# Schematic.net
KiCad netlist of a schematic drawn in EAGLE
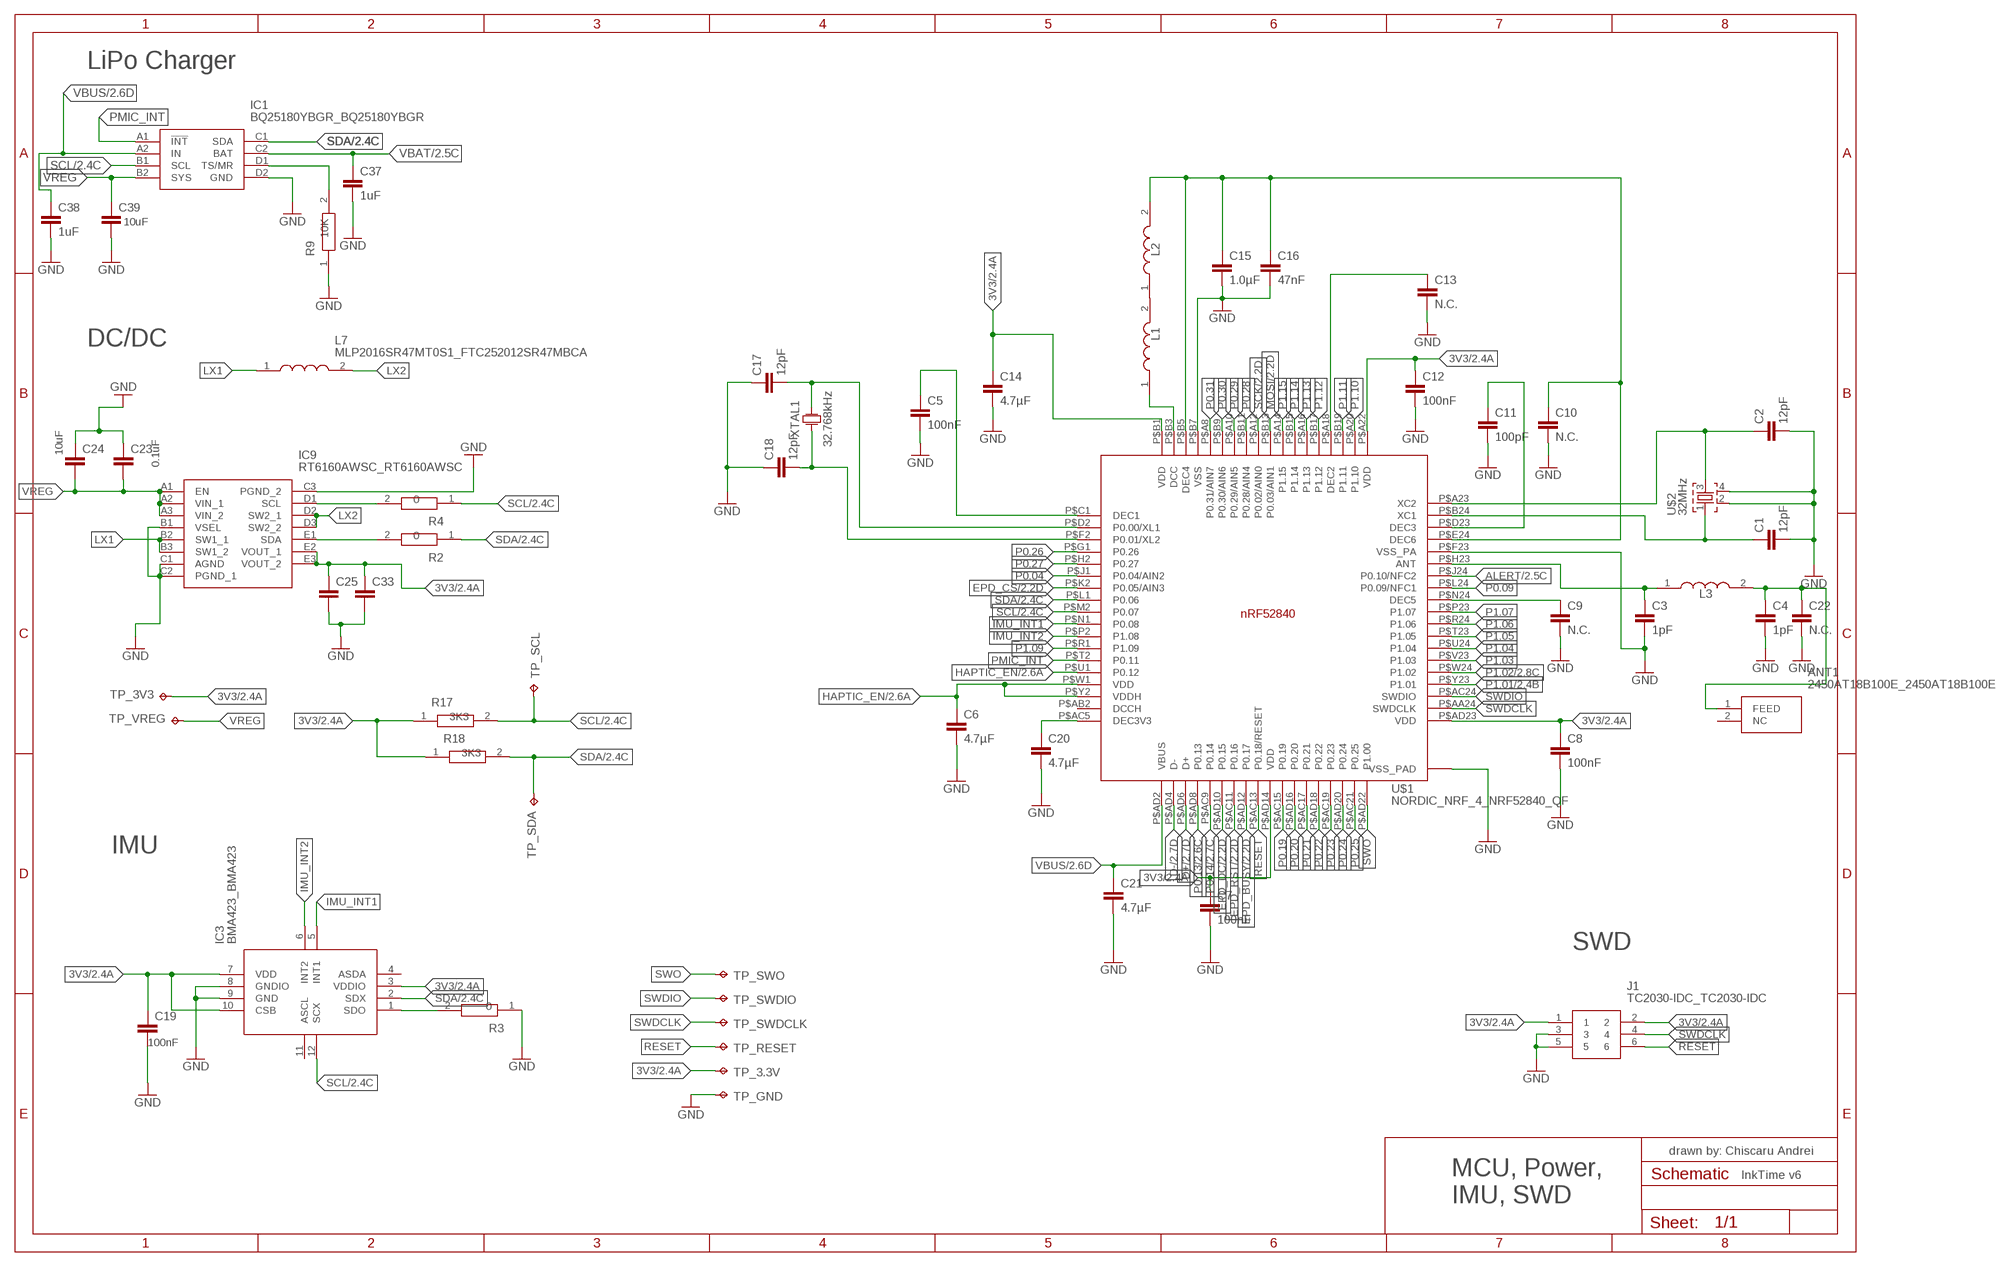
[diagram p0: schematic, sheet 1, part 1 of 2]
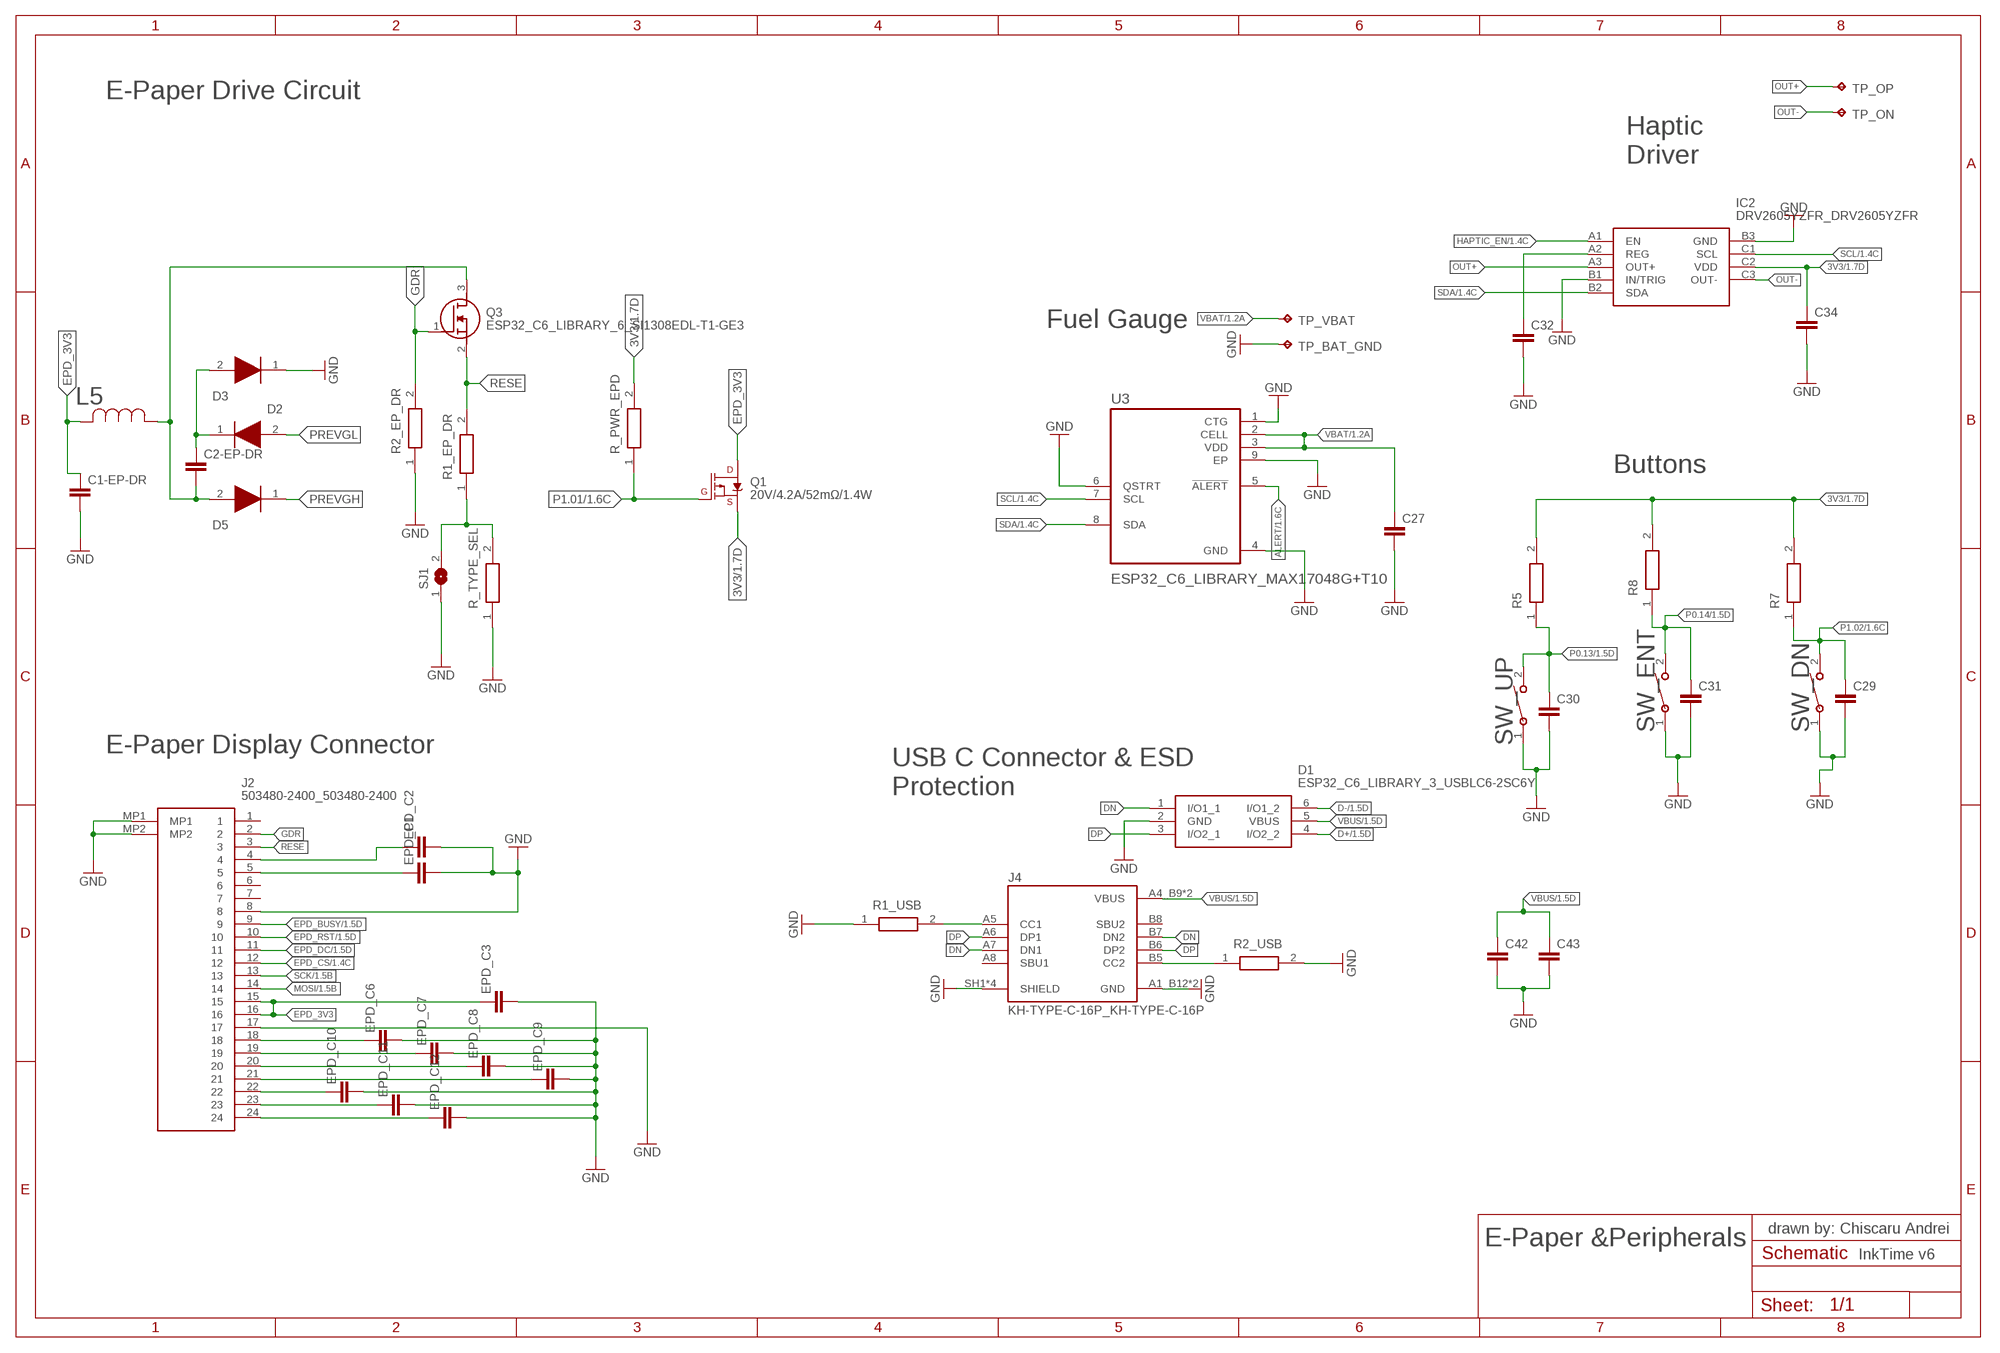
[diagram p1: schematic, sheet 1, part 2 of 2]

(export (version "E")
  (design (tool "Eeschema 10.0.6"))
  (components
    (comp (ref "ANT1")
      (value "2450AT18B100E_2450AT18B100E")
      (footprint "eagle-import:2450AT18B100E_ANTC3216X140N")
      (fields
        (field (name "ARROW_PART_NUMBER") "2450AT18B100E")
        (field (name "MOUSER_PART_NUMBER") "609-2450AT18B100E")
      )
      (libsource (lib "eagle-import") (part "2450AT18B100E_2450AT18B100E"))
    )
    (comp (ref "C1")
      (value "12pF")
      (footprint "eagle-import:NORDIC_NRF_3_RESC0201_L")
      (libsource (lib "eagle-import") (part "NORDIC_NRF_3_CAPACITOR_0201_L"))
    )
    (comp (ref "C1-EP-DR")
      (value "10uF")
      (footprint "eagle-import:NORDIC_NRF_3_RESC0201_L")
      (libsource (lib "eagle-import") (part "NORDIC_NRF_3_CAPACITOR_0201_L"))
    )
    (comp (ref "C2")
      (value "12pF")
      (footprint "eagle-import:NORDIC_NRF_3_RESC0201_L")
      (libsource (lib "eagle-import") (part "NORDIC_NRF_3_CAPACITOR_0201_L"))
    )
    (comp (ref "C2-EP-DR")
      (value "4.7uF/25V")
      (footprint "eagle-import:NORDIC_NRF_3_RESC0201_L")
      (libsource (lib "eagle-import") (part "NORDIC_NRF_3_CAPACITOR_0201_L"))
    )
    (comp (ref "C3")
      (value "1pF")
      (footprint "eagle-import:NORDIC_NRF_3_RESC0201_L")
      (libsource (lib "eagle-import") (part "NORDIC_NRF_3_CAPACITOR_0201_L"))
    )
    (comp (ref "C4")
      (value "1pF")
      (footprint "eagle-import:NORDIC_NRF_3_RESC0201_L")
      (libsource (lib "eagle-import") (part "NORDIC_NRF_3_CAPACITOR_0201_L"))
    )
    (comp (ref "C5")
      (value "100nF")
      (footprint "eagle-import:NORDIC_NRF_3_RESC0201_L")
      (libsource (lib "eagle-import") (part "NORDIC_NRF_3_CAPACITOR_0201_L"))
    )
    (comp (ref "C6")
      (value "4.7µF")
      (footprint "eagle-import:NORDIC_NRF_3_RESC0201_L")
      (libsource (lib "eagle-import") (part "NORDIC_NRF_3_CAPACITOR_0201_L"))
    )
    (comp (ref "C7")
      (value "100nF")
      (footprint "eagle-import:NORDIC_NRF_3_RESC0201_L")
      (libsource (lib "eagle-import") (part "NORDIC_NRF_3_CAPACITOR_0201_L"))
    )
    (comp (ref "C8")
      (value "100nF")
      (footprint "eagle-import:NORDIC_NRF_3_RESC0201_L")
      (libsource (lib "eagle-import") (part "NORDIC_NRF_3_CAPACITOR_0201_L"))
    )
    (comp (ref "C9")
      (value "N.C.")
      (footprint "eagle-import:NORDIC_NRF_3_RESC0201_L")
      (libsource (lib "eagle-import") (part "NORDIC_NRF_3_CAPACITOR_0201_L"))
    )
    (comp (ref "C10")
      (value "N.C.")
      (footprint "eagle-import:NORDIC_NRF_3_RESC0201_L")
      (libsource (lib "eagle-import") (part "NORDIC_NRF_3_CAPACITOR_0201_L"))
    )
    (comp (ref "C11")
      (value "100pF")
      (footprint "eagle-import:NORDIC_NRF_3_RESC0201_L")
      (libsource (lib "eagle-import") (part "NORDIC_NRF_3_CAPACITOR_0201_L"))
    )
    (comp (ref "C12")
      (value "100nF")
      (footprint "eagle-import:NORDIC_NRF_3_RESC0201_L")
      (libsource (lib "eagle-import") (part "NORDIC_NRF_3_CAPACITOR_0201_L"))
    )
    (comp (ref "C13")
      (value "N.C.")
      (footprint "eagle-import:NORDIC_NRF_3_RESC0201_L")
      (libsource (lib "eagle-import") (part "NORDIC_NRF_3_CAPACITOR_0201_L"))
    )
    (comp (ref "C14")
      (value "4.7µF")
      (footprint "eagle-import:NORDIC_NRF_3_RESC0201_L")
      (libsource (lib "eagle-import") (part "NORDIC_NRF_3_CAPACITOR_0201_L"))
    )
    (comp (ref "C15")
      (value "1.0µF")
      (footprint "eagle-import:NORDIC_NRF_3_RESC0201_L")
      (libsource (lib "eagle-import") (part "NORDIC_NRF_3_CAPACITOR_0201_L"))
    )
    (comp (ref "C16")
      (value "47nF")
      (footprint "eagle-import:NORDIC_NRF_3_RESC0201_L")
      (libsource (lib "eagle-import") (part "NORDIC_NRF_3_CAPACITOR_0201_L"))
    )
    (comp (ref "C17")
      (value "12pF")
      (footprint "eagle-import:NORDIC_NRF_3_RESC0201_L")
      (libsource (lib "eagle-import") (part "NORDIC_NRF_3_CAPACITOR_0201_L"))
    )
    (comp (ref "C18")
      (value "12pF")
      (footprint "eagle-import:NORDIC_NRF_3_RESC0201_L")
      (libsource (lib "eagle-import") (part "NORDIC_NRF_3_CAPACITOR_0201_L"))
    )
    (comp (ref "C19")
      (value "100nF")
      (footprint "eagle-import:NORDIC_NRF_3_RESC0201_L")
      (libsource (lib "eagle-import") (part "NORDIC_NRF_3_CAPACITOR_0201_L"))
    )
    (comp (ref "C20")
      (value "4.7µF")
      (footprint "eagle-import:NORDIC_NRF_3_RESC0201_L")
      (libsource (lib "eagle-import") (part "NORDIC_NRF_3_CAPACITOR_0201_L"))
    )
    (comp (ref "C21")
      (value "4.7µF")
      (footprint "eagle-import:NORDIC_NRF_3_RESC0201_L")
      (libsource (lib "eagle-import") (part "NORDIC_NRF_3_CAPACITOR_0201_L"))
    )
    (comp (ref "C22")
      (value "N.C.")
      (footprint "eagle-import:NORDIC_NRF_3_RESC0201_L")
      (libsource (lib "eagle-import") (part "NORDIC_NRF_3_CAPACITOR_0201_L"))
    )
    (comp (ref "C23")
      (value "0.1uF")
      (footprint "eagle-import:NORDIC_NRF_3_RESC0201_L")
      (libsource (lib "eagle-import") (part "NORDIC_NRF_3_CAPACITOR_0201_L"))
    )
    (comp (ref "C24")
      (value "10uF")
      (footprint "eagle-import:NORDIC_NRF_3_RESC0201_L")
      (libsource (lib "eagle-import") (part "NORDIC_NRF_3_CAPACITOR_0201_L"))
    )
    (comp (ref "C25")
      (value "22uF")
      (footprint "eagle-import:NORDIC_NRF_3_RESC0201_L")
      (libsource (lib "eagle-import") (part "NORDIC_NRF_3_CAPACITOR_0201_L"))
    )
    (comp (ref "C27")
      (value "0.1uF")
      (footprint "eagle-import:NORDIC_NRF_3_RESC0201_L")
      (libsource (lib "eagle-import") (part "NORDIC_NRF_3_CAPACITOR_0201_L"))
    )
    (comp (ref "C29")
      (value "1uF")
      (footprint "eagle-import:NORDIC_NRF_3_RESC0201_L")
      (libsource (lib "eagle-import") (part "NORDIC_NRF_3_CAPACITOR_0201_L"))
    )
    (comp (ref "C30")
      (value "1uF")
      (footprint "eagle-import:NORDIC_NRF_3_RESC0201_L")
      (libsource (lib "eagle-import") (part "NORDIC_NRF_3_CAPACITOR_0201_L"))
    )
    (comp (ref "C31")
      (value "1uF")
      (footprint "eagle-import:NORDIC_NRF_3_RESC0201_L")
      (libsource (lib "eagle-import") (part "NORDIC_NRF_3_CAPACITOR_0201_L"))
    )
    (comp (ref "C32")
      (value "1uF")
      (footprint "eagle-import:NORDIC_NRF_3_RESC0201_L")
      (libsource (lib "eagle-import") (part "NORDIC_NRF_3_CAPACITOR_0201_L"))
    )
    (comp (ref "C33")
      (value "22uF")
      (footprint "eagle-import:NORDIC_NRF_3_RESC0201_L")
      (libsource (lib "eagle-import") (part "NORDIC_NRF_3_CAPACITOR_0201_L"))
    )
    (comp (ref "C34")
      (value "0.1uF")
      (footprint "eagle-import:NORDIC_NRF_3_RESC0201_L")
      (libsource (lib "eagle-import") (part "NORDIC_NRF_3_CAPACITOR_0201_L"))
    )
    (comp (ref "C37")
      (value "1uF")
      (footprint "eagle-import:NORDIC_NRF_3_RESC0201_L")
      (libsource (lib "eagle-import") (part "NORDIC_NRF_3_CAPACITOR_0201_L"))
    )
    (comp (ref "C38")
      (value "1uF")
      (footprint "eagle-import:NORDIC_NRF_3_RESC0201_L")
      (libsource (lib "eagle-import") (part "NORDIC_NRF_3_CAPACITOR_0201_L"))
    )
    (comp (ref "C39")
      (value "10uF")
      (footprint "eagle-import:NORDIC_NRF_3_RESC0201_L")
      (libsource (lib "eagle-import") (part "NORDIC_NRF_3_CAPACITOR_0201_L"))
    )
    (comp (ref "C42")
      (value "0.1uF")
      (footprint "eagle-import:NORDIC_NRF_3_RESC0201_L")
      (libsource (lib "eagle-import") (part "NORDIC_NRF_3_CAPACITOR_0201_L"))
    )
    (comp (ref "C43")
      (value "4.7uF")
      (footprint "eagle-import:NORDIC_NRF_3_RESC0201_L")
      (libsource (lib "eagle-import") (part "NORDIC_NRF_3_CAPACITOR_0201_L"))
    )
    (comp (ref "D1")
      (value "ESP32_C6_LIBRARY_3_USBLC6-2SC6Y")
      (footprint "eagle-import:ESP32_C6_LIBRARY_3_SOT95P280X145-6N")
      (fields (field (name "MF") "STMicroelectronics") (field (name "MP") "USBLC6-2SC6Y"))
      (libsource (lib "eagle-import") (part "ESP32_C6_LIBRARY_3_USBLC6-2SC6Y"))
    )
    (comp (ref "D2")
      (value "ESP32_C6_LIBRARY_5_MBR0530")
      (footprint "eagle-import:ESP32_C6_LIBRARY_5_SOD3716X135N")
      (fields (field (name "MF") "ON Semiconductor") (field (name "MP") "MBR0530"))
      (libsource (lib "eagle-import") (part "ESP32_C6_LIBRARY_5_MBR0530"))
    )
    (comp (ref "D3")
      (value "ESP32_C6_LIBRARY_5_MBR0530")
      (footprint "eagle-import:ESP32_C6_LIBRARY_5_SOD3716X135N")
      (fields (field (name "MF") "ON Semiconductor") (field (name "MP") "MBR0530"))
      (libsource (lib "eagle-import") (part "ESP32_C6_LIBRARY_5_MBR0530"))
    )
    (comp (ref "D5")
      (value "ESP32_C6_LIBRARY_5_MBR0530")
      (footprint "eagle-import:ESP32_C6_LIBRARY_5_SOD3716X135N")
      (fields (field (name "MF") "ON Semiconductor") (field (name "MP") "MBR0530"))
      (libsource (lib "eagle-import") (part "ESP32_C6_LIBRARY_5_MBR0530"))
    )
    (comp (ref "EPD_C1")
      (value "1uF/50V")
      (footprint "eagle-import:NORDIC_NRF_3_RESC0201_L")
      (libsource (lib "eagle-import") (part "NORDIC_NRF_3_CAPACITOR_0201_L"))
    )
    (comp (ref "EPD_C2")
      (value "1uF/50V")
      (footprint "eagle-import:NORDIC_NRF_3_RESC0201_L")
      (libsource (lib "eagle-import") (part "NORDIC_NRF_3_CAPACITOR_0201_L"))
    )
    (comp (ref "EPD_C3")
      (value "0.1uF/50V")
      (footprint "eagle-import:NORDIC_NRF_3_RESC0201_L")
      (libsource (lib "eagle-import") (part "NORDIC_NRF_3_CAPACITOR_0201_L"))
    )
    (comp (ref "EPD_C6")
      (value "1uF/50V")
      (footprint "eagle-import:NORDIC_NRF_3_RESC0201_L")
      (libsource (lib "eagle-import") (part "NORDIC_NRF_3_CAPACITOR_0201_L"))
    )
    (comp (ref "EPD_C7")
      (value "1uF/50V")
      (footprint "eagle-import:NORDIC_NRF_3_RESC0201_L")
      (libsource (lib "eagle-import") (part "NORDIC_NRF_3_CAPACITOR_0201_L"))
    )
    (comp (ref "EPD_C8")
      (value "1uF/50V")
      (footprint "eagle-import:NORDIC_NRF_3_RESC0201_L")
      (libsource (lib "eagle-import") (part "NORDIC_NRF_3_CAPACITOR_0201_L"))
    )
    (comp (ref "EPD_C9")
      (value "1uF/50V")
      (footprint "eagle-import:NORDIC_NRF_3_RESC0201_L")
      (libsource (lib "eagle-import") (part "NORDIC_NRF_3_CAPACITOR_0201_L"))
    )
    (comp (ref "EPD_C10")
      (value "1uF/50V")
      (footprint "eagle-import:NORDIC_NRF_3_RESC0201_L")
      (libsource (lib "eagle-import") (part "NORDIC_NRF_3_CAPACITOR_0201_L"))
    )
    (comp (ref "EPD_C11")
      (value "1uF/50V")
      (footprint "eagle-import:NORDIC_NRF_3_RESC0201_L")
      (libsource (lib "eagle-import") (part "NORDIC_NRF_3_CAPACITOR_0201_L"))
    )
    (comp (ref "EPD_C12")
      (value "1uF/50V")
      (footprint "eagle-import:NORDIC_NRF_3_RESC0201_L")
      (libsource (lib "eagle-import") (part "NORDIC_NRF_3_CAPACITOR_0201_L"))
    )
    (comp (ref "IC1")
      (value "BQ25180YBGR_BQ25180YBGR")
      (footprint "eagle-import:BQ25180YBGR_BGA8C40P2X4_100X155X50")
      (fields
        (field (name "ARROW_PART_NUMBER") "BQ25180YBGR")
        (field (name "MOUSER_PART_NUMBER") "595-BQ25180YBGR")
      )
      (libsource (lib "eagle-import") (part "BQ25180YBGR_BQ25180YBGR"))
    )
    (comp (ref "IC2")
      (value "DRV2605YZFR_DRV2605YZFR")
      (footprint "eagle-import:DRV2605YZFR_BGA9C50P3X3_144X144X62")
      (fields (field (name "ARROW_PART_NUMBER") "DRV2605YZFR"))
      (libsource (lib "eagle-import") (part "DRV2605YZFR_DRV2605YZFR"))
    )
    (comp (ref "IC3")
      (value "BMA423_BMA423")
      (footprint "eagle-import:BMA423_BMA423")
      (fields (field (name "ARROW_PART_NUMBER") "BMA423") (field (name "MOUSER_PART_NUMBER") "262-BMA423"))
      (libsource (lib "eagle-import") (part "BMA423_BMA423"))
    )
    (comp (ref "IC9")
      (value "RT6160AWSC_RT6160AWSC")
      (footprint "eagle-import:RT6160AWSC_BGA15C40P3X5_140X230X60")
      (fields
        (field (name "MANUFACTURER_PART_NUMBER") "RT6160AWSC")
        (field (name "MOUSER_PART_NUMBER") "835-RT6160AWSC")
      )
      (libsource (lib "eagle-import") (part "RT6160AWSC_RT6160AWSC"))
    )
    (comp (ref "J1")
      (value "TC2030-IDC_TC2030-IDC")
      (footprint "eagle-import:TC2030-IDC_TC2030IDC")
      (fields (field (name "MANUFACTURER_PART_NUMBER") "TC2030-IDC"))
      (libsource (lib "eagle-import") (part "TC2030-IDC_TC2030-IDC"))
    )
    (comp (ref "J2")
      (value "503480-2400_503480-2400")
      (footprint "eagle-import:503480-2400_5034802400")
      (fields
        (field (name "MANUFACTURER_PART_NUMBER") "503480-2400")
        (field (name "MOUSER_PART_NUMBER") "538-503480-2400")
      )
      (libsource (lib "eagle-import") (part "503480-2400_503480-2400"))
    )
    (comp (ref "J4")
      (value "KH-TYPE-C-16P_KH-TYPE-C-16P")
      (footprint "eagle-import:KH-TYPE-C-16P_KINGHELM_KH-TYPE-C-16P")
      (fields (field (name "MF") "kinghelm") (field (name "MP") "KH-TYPE-C-16P"))
      (libsource (lib "eagle-import") (part "KH-TYPE-C-16P_KH-TYPE-C-16P"))
    )
    (comp (ref "L1")
      (value "10µH")
      (footprint "eagle-import:MLP2016SR47MT0S1_INDC2016X100N")
      (fields (field (name "MANUFACTURER_PART_NUMBER") "FTC252012SR47MBCA"))
      (libsource (lib "eagle-import") (part "MLP2016SR47MT0S1_FTC252012SR47MBCA"))
    )
    (comp (ref "L2")
      (value "15nH")
      (footprint "eagle-import:MLP2016SR47MT0S1_INDC2016X100N")
      (fields (field (name "MANUFACTURER_PART_NUMBER") "FTC252012SR47MBCA"))
      (libsource (lib "eagle-import") (part "MLP2016SR47MT0S1_FTC252012SR47MBCA"))
    )
    (comp (ref "L3")
      (value "3.9nH")
      (footprint "eagle-import:MLP2016SR47MT0S1_INDC2016X100N")
      (fields (field (name "MANUFACTURER_PART_NUMBER") "FTC252012SR47MBCA"))
      (libsource (lib "eagle-import") (part "MLP2016SR47MT0S1_FTC252012SR47MBCA"))
    )
    (comp (ref "L5")
      (value "68uH")
      (footprint "eagle-import:ESP32_C6_LIBRARY_2_IND_4828-WE-TPC_WRE")
      (fields
        (field (name "MANUFACTURER_PART_NUMBER") "744043680")
        (field (name "COPYRIGHT") "Copyright (C) 2024 Ultra Librarian. All rights reserved.")
      )
      (libsource (lib "eagle-import") (part "ESP32_C6_LIBRARY_2_744043680IND_4828-WE-TPC_WRE"))
    )
    (comp (ref "L7")
      (value "MLP2016SR47MT0S1_FTC252012SR47MBCA")
      (footprint "eagle-import:MLP2016SR47MT0S1_INDC2016X100N")
      (fields (field (name "MANUFACTURER_PART_NUMBER") "FTC252012SR47MBCA"))
      (libsource (lib "eagle-import") (part "MLP2016SR47MT0S1_FTC252012SR47MBCA"))
    )
    (comp (ref "Q1")
      (value "20V/4.2A/52mΩ/1.4W")
      (footprint "eagle-import:ESP32_C6_LIBRARY_4_ESP32_C6_LIBRARY_4_ESP32_C6_LIBRARY_4_ESP32_C6_LIBRARY_4_ESP32_WROVER_SPARKFUN-DISCRETESEMI_SOT23-3")
      (libsource (lib "eagle-import") (part "ESP32_C6_LIBRARY_4_ESP32_WROVER_SPARKFUN-DISCRETESEMI_MOSFET_PCH-DMG2305UX-7"))
    )
    (comp (ref "Q3")
      (value "ESP32_C6_LIBRARY_6_SI1308EDL-T1-GE3")
      (footprint "eagle-import:ESP32_C6_LIBRARY_6_SOT65P210X110-3N")
      (fields (field (name "MF") "Vishay Siliconix") (field (name "MP") "SI1308EDL-T1-GE3"))
      (libsource (lib "eagle-import") (part "ESP32_C6_LIBRARY_6_SI1308EDL-T1-GE3"))
    )
    (comp (ref "R1_EP_DR")
      (value "0.47")
      (footprint "eagle-import:CPF0201D7K68C1_0201")
      (libsource (lib "eagle-import") (part "CPF0201D7K68C1_CPF0201D7K68C1"))
    )
    (comp (ref "R1_USB")
      (value "5K1")
      (footprint "eagle-import:CPF0201D7K68C1_0201")
      (libsource (lib "eagle-import") (part "CPF0201D7K68C1_CPF0201D7K68C1"))
    )
    (comp (ref "R2")
      (value "0")
      (footprint "eagle-import:CPF0201D7K68C1_0201")
      (libsource (lib "eagle-import") (part "CPF0201D7K68C1_CPF0201D7K68C1"))
    )
    (comp (ref "R2_EP_DR")
      (value "10K")
      (footprint "eagle-import:CPF0201D7K68C1_0201")
      (libsource (lib "eagle-import") (part "CPF0201D7K68C1_CPF0201D7K68C1"))
    )
    (comp (ref "R2_USB")
      (value "5K1")
      (footprint "eagle-import:CPF0201D7K68C1_0201")
      (libsource (lib "eagle-import") (part "CPF0201D7K68C1_CPF0201D7K68C1"))
    )
    (comp (ref "R3")
      (value "0")
      (footprint "eagle-import:CPF0201D7K68C1_0201")
      (libsource (lib "eagle-import") (part "CPF0201D7K68C1_CPF0201D7K68C1"))
    )
    (comp (ref "R4")
      (value "0")
      (footprint "eagle-import:CPF0201D7K68C1_0201")
      (libsource (lib "eagle-import") (part "CPF0201D7K68C1_CPF0201D7K68C1"))
    )
    (comp (ref "R5")
      (value "10K")
      (footprint "eagle-import:CPF0201D7K68C1_0201")
      (libsource (lib "eagle-import") (part "CPF0201D7K68C1_CPF0201D7K68C1"))
    )
    (comp (ref "R7")
      (value "10K")
      (footprint "eagle-import:CPF0201D7K68C1_0201")
      (libsource (lib "eagle-import") (part "CPF0201D7K68C1_CPF0201D7K68C1"))
    )
    (comp (ref "R8")
      (value "10K")
      (footprint "eagle-import:CPF0201D7K68C1_0201")
      (libsource (lib "eagle-import") (part "CPF0201D7K68C1_CPF0201D7K68C1"))
    )
    (comp (ref "R9")
      (value "10K")
      (footprint "eagle-import:CPF0201D7K68C1_0201")
      (libsource (lib "eagle-import") (part "CPF0201D7K68C1_CPF0201D7K68C1"))
    )
    (comp (ref "R17")
      (value "3K3")
      (footprint "eagle-import:CPF0201D7K68C1_0201")
      (libsource (lib "eagle-import") (part "CPF0201D7K68C1_CPF0201D7K68C1"))
    )
    (comp (ref "R18")
      (value "3K3")
      (footprint "eagle-import:CPF0201D7K68C1_0201")
      (libsource (lib "eagle-import") (part "CPF0201D7K68C1_CPF0201D7K68C1"))
    )
    (comp (ref "R_PWR_EPD")
      (value "10K")
      (footprint "eagle-import:CPF0201D7K68C1_0201")
      (libsource (lib "eagle-import") (part "CPF0201D7K68C1_CPF0201D7K68C1"))
    )
    (comp (ref "R_TYPE_SEL")
      (value "2.2")
      (footprint "eagle-import:CPF0201D7K68C1_0201")
      (libsource (lib "eagle-import") (part "CPF0201D7K68C1_CPF0201D7K68C1"))
    )
    (comp (ref "SJ1")
      (value "ESP32_C6_LIBRARY_7_JUMPER_SJ")
      (footprint "eagle-import:ESP32_C6_LIBRARY_7_JUMPER_SJ")
      (libsource (lib "eagle-import") (part "ESP32_C6_LIBRARY_7_JUMPER_SJ"))
    )
    (comp (ref "SW_DN")
      (value "2025-10-22_07-23-44_LIBRARY_EVP-AKE31ASW_EVP-AKE31A_PAN")
      (footprint "eagle-import:2025-10-22_07-23-44_LIBRARY_SW_EVP-AKE31A_PAN")
      (fields
        (field (name "MANUFACTURER_PART_NUMBER") "EVP-AKE31A")
        (field (name "COPYRIGHT") "Copyright (C) 2025 Ultra Librarian. All rights reserved.")
      )
      (libsource (lib "eagle-import") (part "2025-10-22_07-23-44_LIBRARY_EVP-AKE31ASW_EVP-AKE31A_PAN"))
    )
    (comp (ref "SW_ENT")
      (value "2025-10-22_07-23-44_LIBRARY_EVP-AKE31ASW_EVP-AKE31A_PAN")
      (footprint "eagle-import:2025-10-22_07-23-44_LIBRARY_SW_EVP-AKE31A_PAN")
      (fields
        (field (name "MANUFACTURER_PART_NUMBER") "EVP-AKE31A")
        (field (name "COPYRIGHT") "Copyright (C) 2025 Ultra Librarian. All rights reserved.")
      )
      (libsource (lib "eagle-import") (part "2025-10-22_07-23-44_LIBRARY_EVP-AKE31ASW_EVP-AKE31A_PAN"))
    )
    (comp (ref "SW_UP")
      (value "2025-10-22_07-23-44_LIBRARY_EVP-AKE31ASW_EVP-AKE31A_PAN")
      (footprint "eagle-import:2025-10-22_07-23-44_LIBRARY_SW_EVP-AKE31A_PAN")
      (fields
        (field (name "MANUFACTURER_PART_NUMBER") "EVP-AKE31A")
        (field (name "COPYRIGHT") "Copyright (C) 2025 Ultra Librarian. All rights reserved.")
      )
      (libsource (lib "eagle-import") (part "2025-10-22_07-23-44_LIBRARY_EVP-AKE31ASW_EVP-AKE31A_PAN"))
    )
    (comp (ref "TP_3.3V")
      (value "HECTOR_WATCH_1_TPTP20R")
      (footprint "eagle-import:HECTOR_WATCH_1_TP20R")
      (libsource (lib "eagle-import") (part "HECTOR_WATCH_1_TPTP20R"))
    )
    (comp (ref "TP_3V3")
      (value "HECTOR_WATCH_1_TPTP20R")
      (footprint "eagle-import:HECTOR_WATCH_1_TP20R")
      (libsource (lib "eagle-import") (part "HECTOR_WATCH_1_TPTP20R"))
    )
    (comp (ref "TP_BAT_GND")
      (value "HECTOR_WATCH_1_TPTP20R")
      (footprint "eagle-import:HECTOR_WATCH_1_TP20R")
      (libsource (lib "eagle-import") (part "HECTOR_WATCH_1_TPTP20R"))
    )
    (comp (ref "TP_GND")
      (value "HECTOR_WATCH_1_TPTP20R")
      (footprint "eagle-import:HECTOR_WATCH_1_TP20R")
      (libsource (lib "eagle-import") (part "HECTOR_WATCH_1_TPTP20R"))
    )
    (comp (ref "TP_ON")
      (value "HECTOR_WATCH_1_TPTP20R")
      (footprint "eagle-import:HECTOR_WATCH_1_TP20R")
      (libsource (lib "eagle-import") (part "HECTOR_WATCH_1_TPTP20R"))
    )
    (comp (ref "TP_OP")
      (value "HECTOR_WATCH_1_TPTP20R")
      (footprint "eagle-import:HECTOR_WATCH_1_TP20R")
      (libsource (lib "eagle-import") (part "HECTOR_WATCH_1_TPTP20R"))
    )
    (comp (ref "TP_RESET")
      (value "HECTOR_WATCH_1_TPTP20R")
      (footprint "eagle-import:HECTOR_WATCH_1_TP20R")
      (libsource (lib "eagle-import") (part "HECTOR_WATCH_1_TPTP20R"))
    )
    (comp (ref "TP_SCL")
      (value "HECTOR_WATCH_1_TPTP20R")
      (footprint "eagle-import:HECTOR_WATCH_1_TP20R")
      (libsource (lib "eagle-import") (part "HECTOR_WATCH_1_TPTP20R"))
    )
    (comp (ref "TP_SDA")
      (value "HECTOR_WATCH_1_TPTP20R")
      (footprint "eagle-import:HECTOR_WATCH_1_TP20R")
      (libsource (lib "eagle-import") (part "HECTOR_WATCH_1_TPTP20R"))
    )
    (comp (ref "TP_SWDCLK")
      (value "HECTOR_WATCH_1_TPTP20R")
      (footprint "eagle-import:HECTOR_WATCH_1_TP20R")
      (libsource (lib "eagle-import") (part "HECTOR_WATCH_1_TPTP20R"))
    )
    (comp (ref "TP_SWDIO")
      (value "HECTOR_WATCH_1_TPTP20R")
      (footprint "eagle-import:HECTOR_WATCH_1_TP20R")
      (libsource (lib "eagle-import") (part "HECTOR_WATCH_1_TPTP20R"))
    )
    (comp (ref "TP_SWO")
      (value "HECTOR_WATCH_1_TPTP20R")
      (footprint "eagle-import:HECTOR_WATCH_1_TP20R")
      (libsource (lib "eagle-import") (part "HECTOR_WATCH_1_TPTP20R"))
    )
    (comp (ref "TP_VBAT")
      (value "HECTOR_WATCH_1_TPTP20R")
      (footprint "eagle-import:HECTOR_WATCH_1_TP20R")
      (libsource (lib "eagle-import") (part "HECTOR_WATCH_1_TPTP20R"))
    )
    (comp (ref "TP_VREG")
      (value "HECTOR_WATCH_1_TPTP20R")
      (footprint "eagle-import:HECTOR_WATCH_1_TP20R")
      (libsource (lib "eagle-import") (part "HECTOR_WATCH_1_TPTP20R"))
    )
    (comp (ref "U$1")
      (value "NORDIC_NRF_4_NRF52840_QF")
      (footprint "eagle-import:NORDIC_NRF_4_AQFN50P700X700X85_HS-74N")
      (libsource (lib "eagle-import") (part "NORDIC_NRF_4_NRF52840_QF"))
    )
    (comp (ref "U$2")
      (value "32MHz")
      (footprint "eagle-import:NORDIC_NRF_BT-XTAL_2016_N")
      (libsource (lib "eagle-import") (part "NORDIC_NRF_XTAL_32MHZ"))
    )
    (comp (ref "U3")
      (value "ESP32_C6_LIBRARY_MAX17048G+T10")
      (footprint "eagle-import:ESP32_C6_LIBRARY_SON50P200X200X80-9N")
      (fields (field (name "MF") "Analog Devices") (field (name "MP") "MAX17048G+T10"))
      (libsource (lib "eagle-import") (part "ESP32_C6_LIBRARY_MAX17048G+T10"))
    )
    (comp (ref "XTAL1")
      (value "32.768kHz")
      (footprint "eagle-import:XTAL_ABS07-32.768KHZ-T")
      (fields
        (field (name "MANUFACTURER") "Abracon LLC")
        (field (name "MPN") "ABS07-32.768KHZ-T")
        (field (name "TOLERANCE") "±20 ppm")
      )
      (libsource (lib "eagle-import") (part "ABSO7"))
    )
  )
  (nets
    (net (code "1") (name "3V3{slash}1.7D") (class "Default")
      (node (ref "C34") (pin "1") (pinfunction "1_1") (pintype "passive"))
      (node (ref "IC2") (pin "C2") (pinfunction "VDD_C2") (pintype "bidirectional"))
      (node (ref "Q1") (pin "2") (pinfunction "S_2") (pintype "bidirectional"))
      (node (ref "R5") (pin "2") (pinfunction "2_2") (pintype "bidirectional"))
      (node (ref "R7") (pin "2") (pinfunction "2_2") (pintype "bidirectional"))
      (node (ref "R8") (pin "2") (pinfunction "2_2") (pintype "bidirectional"))
      (node (ref "R_PWR_EPD") (pin "2") (pinfunction "2_2") (pintype "bidirectional"))
    )
    (net (code "2") (name "3V3{slash}2.4A") (class "Default")
      (node (ref "C12") (pin "1") (pinfunction "1_1") (pintype "passive"))
      (node (ref "C14") (pin "1") (pinfunction "1_1") (pintype "passive"))
      (node (ref "C19") (pin "1") (pinfunction "1_1") (pintype "passive"))
      (node (ref "C25") (pin "1") (pinfunction "1_1") (pintype "passive"))
      (node (ref "C33") (pin "1") (pinfunction "1_1") (pintype "passive"))
      (node (ref "C7") (pin "1") (pinfunction "1_1") (pintype "passive"))
      (node (ref "C8") (pin "1") (pinfunction "1_1") (pintype "passive"))
      (node (ref "IC3") (pin "10") (pinfunction "CSB_10") (pintype "bidirectional"))
      (node (ref "IC3") (pin "3") (pinfunction "VDDIO_3") (pintype "bidirectional"))
      (node (ref "IC3") (pin "7") (pinfunction "VDD_7") (pintype "bidirectional"))
      (node (ref "IC9") (pin "E2") (pinfunction "VOUT_1_E2") (pintype "bidirectional"))
      (node (ref "IC9") (pin "E3") (pinfunction "VOUT_2_E3") (pintype "bidirectional"))
      (node (ref "J1") (pin "1") (pinfunction "1_1") (pintype "bidirectional"))
      (node (ref "R17") (pin "1") (pinfunction "1_1") (pintype "bidirectional"))
      (node (ref "R18") (pin "1") (pinfunction "1_1") (pintype "bidirectional"))
      (node (ref "TP_3.3V") (pin "TP") (pinfunction "TP_TP") (pintype "input"))
      (node (ref "TP_3V3") (pin "TP") (pinfunction "TP_TP") (pintype "input"))
      (node (ref "U$1") (pin "P$A22") (pinfunction "VDD_P$A22") (pintype "power_in"))
      (node (ref "U$1") (pin "P$AD14") (pinfunction "VDD_P$AD14") (pintype "power_in"))
      (node (ref "U$1") (pin "P$AD23") (pinfunction "VDD_P$AD23") (pintype "power_in"))
      (node (ref "U$1") (pin "P$B1") (pinfunction "VDD_P$B1") (pintype "power_in"))
    )
    (net (code "3") (name "ALERT{slash}1.6C") (class "Default")
      (node (ref "U3") (pin "5") (pinfunction "~{ALERT}_5") (pintype "output"))
    )
    (net (code "4") (name "ALERT{slash}2.5C") (class "Default")
      (node (ref "U$1") (pin "P$J24") (pinfunction "P0.10/NFC2_P$J24") (pintype "bidirectional"))
    )
    (net (code "5") (name "D+{slash}1.5D") (class "Default")
      (node (ref "D1") (pin "4") (pinfunction "I/O2_2_4") (pintype "bidirectional"))
    )
    (net (code "6") (name "D+{slash}2.7D") (class "Default")
      (node (ref "U$1") (pin "P$AD6") (pinfunction "D+_P$AD6") (pintype "bidirectional"))
    )
    (net (code "7") (name "D-{slash}1.5D") (class "Default")
      (node (ref "D1") (pin "6") (pinfunction "I/O1_2_6") (pintype "bidirectional"))
    )
    (net (code "8") (name "D-{slash}2.7D") (class "Default")
      (node (ref "U$1") (pin "P$AD4") (pinfunction "D-_P$AD4") (pintype "bidirectional"))
    )
    (net (code "9") (name "DN") (class "Default")
      (node (ref "D1") (pin "1") (pinfunction "I/O1_1_1") (pintype "bidirectional"))
      (node (ref "J4") (pin "A7") (pinfunction "DN1_A7") (pintype "bidirectional"))
      (node (ref "J4") (pin "B7") (pinfunction "DN2_B7") (pintype "bidirectional"))
    )
    (net (code "10") (name "DP") (class "Default")
      (node (ref "D1") (pin "3") (pinfunction "I/O2_1_3") (pintype "bidirectional"))
      (node (ref "J4") (pin "A6") (pinfunction "DP1_A6") (pintype "bidirectional"))
      (node (ref "J4") (pin "B6") (pinfunction "DP2_B6") (pintype "bidirectional"))
    )
    (net (code "11") (name "EPD_3V3") (class "Default")
      (node (ref "C1-EP-DR") (pin "1") (pinfunction "1_1") (pintype "passive"))
      (node (ref "EPD_C3") (pin "1") (pinfunction "1_1") (pintype "passive"))
      (node (ref "J2") (pin "15") (pinfunction "15_15") (pintype "bidirectional"))
      (node (ref "J2") (pin "16") (pinfunction "16_16") (pintype "bidirectional"))
      (node (ref "L5") (pin "2") (pinfunction "2_2") (pintype "passive"))
      (node (ref "Q1") (pin "3") (pinfunction "D_3") (pintype "bidirectional"))
    )
    (net (code "12") (name "EPD_BUSY{slash}1.5D") (class "Default")
      (node (ref "J2") (pin "9") (pinfunction "9_9") (pintype "bidirectional"))
    )
    (net (code "13") (name "EPD_BUSY{slash}2.2D") (class "Default")
      (node (ref "U$1") (pin "P$AD12") (pinfunction "P0.17_P$AD12") (pintype "bidirectional"))
    )
    (net (code "14") (name "EPD_CS{slash}1.4C") (class "Default")
      (node (ref "J2") (pin "12") (pinfunction "12_12") (pintype "bidirectional"))
    )
    (net (code "15") (name "EPD_CS{slash}2.2D") (class "Default")
      (node (ref "U$1") (pin "P$K2") (pinfunction "P0.05/AIN3_P$K2") (pintype "bidirectional"))
    )
    (net (code "16") (name "EPD_DC{slash}1.5D") (class "Default")
      (node (ref "J2") (pin "11") (pinfunction "11_11") (pintype "bidirectional"))
    )
    (net (code "17") (name "EPD_DC{slash}2.2D") (class "Default")
      (node (ref "U$1") (pin "P$AD10") (pinfunction "P0.15_P$AD10") (pintype "bidirectional"))
    )
    (net (code "18") (name "EPD_RST{slash}1.5D") (class "Default")
      (node (ref "J2") (pin "10") (pinfunction "10_10") (pintype "bidirectional"))
    )
    (net (code "19") (name "EPD_RST{slash}2.2D") (class "Default")
      (node (ref "U$1") (pin "P$AC11") (pinfunction "P0.16_P$AC11") (pintype "bidirectional"))
    )
    (net (code "20") (name "GDR") (class "Default")
      (node (ref "J2") (pin "2") (pinfunction "2_2") (pintype "bidirectional"))
      (node (ref "Q3") (pin "1") (pinfunction "G_1") (pintype "bidirectional"))
      (node (ref "R2_EP_DR") (pin "2") (pinfunction "2_2") (pintype "bidirectional"))
    )
    (net (code "21") (name "GND") (class "Default")
      (node (ref "C1") (pin "2") (pinfunction "2_2") (pintype "passive"))
      (node (ref "C1-EP-DR") (pin "2") (pinfunction "2_2") (pintype "passive"))
      (node (ref "C10") (pin "2") (pinfunction "2_2") (pintype "passive"))
      (node (ref "C11") (pin "2") (pinfunction "2_2") (pintype "passive"))
      (node (ref "C12") (pin "2") (pinfunction "2_2") (pintype "passive"))
      (node (ref "C13") (pin "2") (pinfunction "2_2") (pintype "passive"))
      (node (ref "C14") (pin "2") (pinfunction "2_2") (pintype "passive"))
      (node (ref "C15") (pin "2") (pinfunction "2_2") (pintype "passive"))
      (node (ref "C16") (pin "2") (pinfunction "2_2") (pintype "passive"))
      (node (ref "C17") (pin "1") (pinfunction "1_1") (pintype "passive"))
      (node (ref "C18") (pin "1") (pinfunction "1_1") (pintype "passive"))
      (node (ref "C19") (pin "2") (pinfunction "2_2") (pintype "passive"))
      (node (ref "C2") (pin "2") (pinfunction "2_2") (pintype "passive"))
      (node (ref "C20") (pin "2") (pinfunction "2_2") (pintype "passive"))
      (node (ref "C21") (pin "2") (pinfunction "2_2") (pintype "passive"))
      (node (ref "C22") (pin "2") (pinfunction "2_2") (pintype "passive"))
      (node (ref "C23") (pin "1") (pinfunction "1_1") (pintype "passive"))
      (node (ref "C24") (pin "1") (pinfunction "1_1") (pintype "passive"))
      (node (ref "C25") (pin "2") (pinfunction "2_2") (pintype "passive"))
      (node (ref "C27") (pin "2") (pinfunction "2_2") (pintype "passive"))
      (node (ref "C29") (pin "2") (pinfunction "2_2") (pintype "passive"))
      (node (ref "C3") (pin "2") (pinfunction "2_2") (pintype "passive"))
      (node (ref "C30") (pin "2") (pinfunction "2_2") (pintype "passive"))
      (node (ref "C31") (pin "2") (pinfunction "2_2") (pintype "passive"))
      (node (ref "C32") (pin "2") (pinfunction "2_2") (pintype "passive"))
      (node (ref "C33") (pin "2") (pinfunction "2_2") (pintype "passive"))
      (node (ref "C34") (pin "2") (pinfunction "2_2") (pintype "passive"))
      (node (ref "C37") (pin "2") (pinfunction "2_2") (pintype "passive"))
      (node (ref "C38") (pin "2") (pinfunction "2_2") (pintype "passive"))
      (node (ref "C39") (pin "2") (pinfunction "2_2") (pintype "passive"))
      (node (ref "C4") (pin "2") (pinfunction "2_2") (pintype "passive"))
      (node (ref "C42") (pin "2") (pinfunction "2_2") (pintype "passive"))
      (node (ref "C43") (pin "2") (pinfunction "2_2") (pintype "passive"))
      (node (ref "C5") (pin "2") (pinfunction "2_2") (pintype "passive"))
      (node (ref "C6") (pin "2") (pinfunction "2_2") (pintype "passive"))
      (node (ref "C7") (pin "2") (pinfunction "2_2") (pintype "passive"))
      (node (ref "C8") (pin "2") (pinfunction "2_2") (pintype "passive"))
      (node (ref "C9") (pin "2") (pinfunction "2_2") (pintype "passive"))
      (node (ref "D1") (pin "2") (pinfunction "GND_2") (pintype "bidirectional"))
      (node (ref "D3") (pin "1") (pinfunction "K_1") (pintype "bidirectional"))
      (node (ref "EPD_C1") (pin "2") (pinfunction "2_2") (pintype "passive"))
      (node (ref "EPD_C10") (pin "2") (pinfunction "2_2") (pintype "passive"))
      (node (ref "EPD_C11") (pin "2") (pinfunction "2_2") (pintype "passive"))
      (node (ref "EPD_C12") (pin "2") (pinfunction "2_2") (pintype "passive"))
      (node (ref "EPD_C2") (pin "2") (pinfunction "2_2") (pintype "passive"))
      (node (ref "EPD_C3") (pin "2") (pinfunction "2_2") (pintype "passive"))
      (node (ref "EPD_C6") (pin "2") (pinfunction "2_2") (pintype "passive"))
      (node (ref "EPD_C7") (pin "2") (pinfunction "2_2") (pintype "passive"))
      (node (ref "EPD_C8") (pin "2") (pinfunction "2_2") (pintype "passive"))
      (node (ref "EPD_C9") (pin "2") (pinfunction "2_2") (pintype "passive"))
      (node (ref "IC1") (pin "D2") (pinfunction "GND_D2") (pintype "bidirectional"))
      (node (ref "IC2") (pin "B1") (pinfunction "IN/TRIG_B1") (pintype "bidirectional"))
      (node (ref "IC2") (pin "B3") (pinfunction "GND_B3") (pintype "bidirectional"))
      (node (ref "IC3") (pin "8") (pinfunction "GNDIO_8") (pintype "bidirectional"))
      (node (ref "IC3") (pin "9") (pinfunction "GND_9") (pintype "bidirectional"))
      (node (ref "IC9") (pin "B1") (pinfunction "VSEL_B1") (pintype "bidirectional"))
      (node (ref "IC9") (pin "C1") (pinfunction "AGND_C1") (pintype "bidirectional"))
      (node (ref "IC9") (pin "C2") (pinfunction "PGND_1_C2") (pintype "bidirectional"))
      (node (ref "IC9") (pin "C3") (pinfunction "PGND_2_C3") (pintype "bidirectional"))
      (node (ref "J1") (pin "3") (pinfunction "3_3") (pintype "bidirectional"))
      (node (ref "J1") (pin "5") (pinfunction "5_5") (pintype "bidirectional"))
      (node (ref "J2") (pin "17") (pinfunction "17_17") (pintype "bidirectional"))
      (node (ref "J2") (pin "8") (pinfunction "8_8") (pintype "bidirectional"))
      (node (ref "J2") (pin "MP1") (pinfunction "MP1_MP1") (pintype "bidirectional"))
      (node (ref "J2") (pin "MP2") (pinfunction "MP2_MP2") (pintype "bidirectional"))
      (node (ref "J4") (pin "A12_B1") (pinfunction "GND_A12_B1") (pintype "power_in"))
      (node (ref "J4") (pin "A1_B12") (pinfunction "GND_A1_B12") (pintype "power_in"))
      (node (ref "J4") (pin "SH1") (pinfunction "SHIELD_SH1") (pintype "passive"))
      (node (ref "J4") (pin "SH2") (pinfunction "SHIELD_SH2") (pintype "passive"))
      (node (ref "J4") (pin "SH3") (pinfunction "SHIELD_SH3") (pintype "passive"))
      (node (ref "J4") (pin "SH4") (pinfunction "SHIELD_SH4") (pintype "passive"))
      (node (ref "R1_USB") (pin "1") (pinfunction "1_1") (pintype "bidirectional"))
      (node (ref "R2_EP_DR") (pin "1") (pinfunction "1_1") (pintype "bidirectional"))
      (node (ref "R2_USB") (pin "2") (pinfunction "2_2") (pintype "bidirectional"))
      (node (ref "R3") (pin "1") (pinfunction "1_1") (pintype "bidirectional"))
      (node (ref "R9") (pin "1") (pinfunction "1_1") (pintype "bidirectional"))
      (node (ref "R_TYPE_SEL") (pin "1") (pinfunction "1_1") (pintype "bidirectional"))
      (node (ref "SJ1") (pin "1") (pinfunction "1_1") (pintype "passive"))
      (node (ref "SW_DN") (pin "1") (pinfunction "1_1") (pintype "passive"))
      (node (ref "SW_ENT") (pin "1") (pinfunction "1_1") (pintype "passive"))
      (node (ref "SW_UP") (pin "1") (pinfunction "1_1") (pintype "passive"))
      (node (ref "TP_BAT_GND") (pin "TP") (pinfunction "TP_TP") (pintype "input"))
      (node (ref "TP_GND") (pin "TP") (pinfunction "TP_TP") (pintype "input"))
      (node (ref "U$1") (pin "P$74") (pinfunction "VSS_PAD_P$74") (pintype "bidirectional"))
      (node (ref "U$1") (pin "P$75") (pinfunction "VSS_PAD_P$75") (pintype "bidirectional"))
      (node (ref "U$1") (pin "P$76") (pinfunction "VSS_PAD_P$76") (pintype "bidirectional"))
      (node (ref "U$1") (pin "P$77") (pinfunction "VSS_PAD_P$77") (pintype "bidirectional"))
      (node (ref "U$1") (pin "P$78") (pinfunction "VSS_PAD_P$78") (pintype "bidirectional"))
      (node (ref "U$1") (pin "P$79") (pinfunction "VSS_PAD_P$79") (pintype "bidirectional"))
      (node (ref "U$1") (pin "P$80") (pinfunction "VSS_PAD_P$80") (pintype "bidirectional"))
      (node (ref "U$1") (pin "P$81") (pinfunction "VSS_PAD_P$81") (pintype "bidirectional"))
      (node (ref "U$1") (pin "P$82") (pinfunction "VSS_PAD_P$82") (pintype "bidirectional"))
      (node (ref "U$1") (pin "P$83") (pinfunction "VSS_PAD_P$83") (pintype "bidirectional"))
      (node (ref "U$1") (pin "P$84") (pinfunction "VSS_PAD_P$84") (pintype "bidirectional"))
      (node (ref "U$1") (pin "P$85") (pinfunction "VSS_PAD_P$85") (pintype "bidirectional"))
      (node (ref "U$1") (pin "P$86") (pinfunction "VSS_PAD_P$86") (pintype "bidirectional"))
      (node (ref "U$1") (pin "P$87") (pinfunction "VSS_PAD_P$87") (pintype "bidirectional"))
      (node (ref "U$1") (pin "P$88") (pinfunction "VSS_PAD_P$88") (pintype "bidirectional"))
      (node (ref "U$1") (pin "P$89") (pinfunction "VSS_PAD_P$89") (pintype "bidirectional"))
      (node (ref "U$1") (pin "P$90") (pinfunction "VSS_PAD_P$90") (pintype "bidirectional"))
      (node (ref "U$1") (pin "P$B7") (pinfunction "VSS_P$B7") (pintype "power_in"))
      (node (ref "U$1") (pin "P$F23") (pinfunction "VSS_PA_P$F23") (pintype "bidirectional"))
      (node (ref "U$2") (pin "2") (pinfunction "2_2") (pintype "passive"))
      (node (ref "U$2") (pin "4") (pinfunction "4_4") (pintype "passive"))
      (node (ref "U3") (pin "1") (pinfunction "CTG_1") (pintype "power_in"))
      (node (ref "U3") (pin "4") (pinfunction "GND_4") (pintype "power_in"))
      (node (ref "U3") (pin "6") (pinfunction "QSTRT_6") (pintype "input"))
      (node (ref "U3") (pin "9") (pinfunction "EP_9") (pintype "power_in"))
    )
    (net (code "22") (name "HAPTIC_EN{slash}1.4C") (class "Default")
      (node (ref "IC2") (pin "A1") (pinfunction "EN_A1") (pintype "bidirectional"))
    )
    (net (code "23") (name "HAPTIC_EN{slash}2.6A") (class "Default")
      (node (ref "C6") (pin "1") (pinfunction "1_1") (pintype "passive"))
      (node (ref "U$1") (pin "P$U1") (pinfunction "P0.12_P$U1") (pintype "bidirectional"))
      (node (ref "U$1") (pin "P$W1") (pinfunction "VDD_P$W1") (pintype "power_in"))
      (node (ref "U$1") (pin "P$Y2") (pinfunction "VDDH_P$Y2") (pintype "power_in"))
    )
    (net (code "24") (name "IMU_INT1") (class "Default")
      (node (ref "IC3") (pin "5") (pinfunction "INT1_5") (pintype "bidirectional"))
      (node (ref "U$1") (pin "P$N1") (pinfunction "P0.08_P$N1") (pintype "bidirectional"))
    )
    (net (code "25") (name "IMU_INT2") (class "Default")
      (node (ref "IC3") (pin "6") (pinfunction "INT2_6") (pintype "bidirectional"))
      (node (ref "U$1") (pin "P$P2") (pinfunction "P1.08_P$P2") (pintype "bidirectional"))
    )
    (net (code "26") (name "LX1") (class "Default")
      (node (ref "IC9") (pin "B2") (pinfunction "SW1_1_B2") (pintype "bidirectional"))
      (node (ref "IC9") (pin "B3") (pinfunction "SW1_2_B3") (pintype "bidirectional"))
      (node (ref "L7") (pin "1") (pinfunction "1_1") (pintype "bidirectional"))
    )
    (net (code "27") (name "LX2") (class "Default")
      (node (ref "IC9") (pin "D2") (pinfunction "SW2_1_D2") (pintype "bidirectional"))
      (node (ref "IC9") (pin "D3") (pinfunction "SW2_2_D3") (pintype "bidirectional"))
      (node (ref "L7") (pin "2") (pinfunction "2_2") (pintype "bidirectional"))
    )
    (net (code "28") (name "MOSI{slash}1.5B") (class "Default")
      (node (ref "J2") (pin "14") (pinfunction "14_14") (pintype "bidirectional"))
    )
    (net (code "29") (name "MOSI{slash}2.2D") (class "Default")
      (node (ref "U$1") (pin "P$B13") (pinfunction "P0.03/AIN1_P$B13") (pintype "bidirectional"))
    )
    (net (code "30") (name "Net-(ANT1-FEED)") (class "Default")
      (node (ref "ANT1") (pin "1") (pinfunction "FEED_1") (pintype "input"))
      (node (ref "C22") (pin "1") (pinfunction "1_1") (pintype "passive"))
      (node (ref "C4") (pin "1") (pinfunction "1_1") (pintype "passive"))
      (node (ref "L3") (pin "2") (pinfunction "2_2") (pintype "bidirectional"))
    )
    (net (code "31") (name "Net-(D2-K)") (class "Default")
      (node (ref "C2-EP-DR") (pin "1") (pinfunction "1_1") (pintype "passive"))
      (node (ref "D2") (pin "1") (pinfunction "K_1") (pintype "bidirectional"))
      (node (ref "D3") (pin "2") (pinfunction "A_2") (pintype "bidirectional"))
    )
    (net (code "32") (name "Net-(D5-A)") (class "Default")
      (node (ref "C2-EP-DR") (pin "2") (pinfunction "2_2") (pintype "passive"))
      (node (ref "D5") (pin "2") (pinfunction "A_2") (pintype "bidirectional"))
      (node (ref "L5") (pin "1") (pinfunction "1_1") (pintype "passive"))
      (node (ref "Q3") (pin "3") (pinfunction "D_3") (pintype "bidirectional"))
    )
    (net (code "33") (name "Net-(EPD_C1-Pad1)") (class "Default")
      (node (ref "EPD_C1") (pin "1") (pinfunction "1_1") (pintype "passive"))
      (node (ref "J2") (pin "5") (pinfunction "5_5") (pintype "bidirectional"))
    )
    (net (code "34") (name "Net-(EPD_C2-Pad1)") (class "Default")
      (node (ref "EPD_C2") (pin "1") (pinfunction "1_1") (pintype "passive"))
      (node (ref "J2") (pin "4") (pinfunction "4_4") (pintype "bidirectional"))
    )
    (net (code "35") (name "Net-(EPD_C6-Pad1)") (class "Default")
      (node (ref "EPD_C6") (pin "1") (pinfunction "1_1") (pintype "passive"))
      (node (ref "J2") (pin "18") (pinfunction "18_18") (pintype "bidirectional"))
    )
    (net (code "36") (name "Net-(EPD_C7-Pad1)") (class "Default")
      (node (ref "EPD_C7") (pin "1") (pinfunction "1_1") (pintype "passive"))
      (node (ref "J2") (pin "19") (pinfunction "19_19") (pintype "bidirectional"))
    )
    (net (code "37") (name "Net-(EPD_C8-Pad1)") (class "Default")
      (node (ref "EPD_C8") (pin "1") (pinfunction "1_1") (pintype "passive"))
      (node (ref "J2") (pin "20") (pinfunction "20_20") (pintype "bidirectional"))
    )
    (net (code "38") (name "Net-(EPD_C9-Pad1)") (class "Default")
      (node (ref "EPD_C9") (pin "1") (pinfunction "1_1") (pintype "passive"))
      (node (ref "J2") (pin "21") (pinfunction "21_21") (pintype "bidirectional"))
    )
    (net (code "39") (name "Net-(EPD_C10-Pad1)") (class "Default")
      (node (ref "EPD_C10") (pin "1") (pinfunction "1_1") (pintype "passive"))
      (node (ref "J2") (pin "22") (pinfunction "22_22") (pintype "bidirectional"))
    )
    (net (code "40") (name "Net-(EPD_C11-Pad1)") (class "Default")
      (node (ref "EPD_C11") (pin "1") (pinfunction "1_1") (pintype "passive"))
      (node (ref "J2") (pin "23") (pinfunction "23_23") (pintype "bidirectional"))
    )
    (net (code "41") (name "Net-(EPD_C12-Pad1)") (class "Default")
      (node (ref "EPD_C12") (pin "1") (pinfunction "1_1") (pintype "passive"))
      (node (ref "J2") (pin "24") (pinfunction "24_24") (pintype "bidirectional"))
    )
    (net (code "42") (name "Net-(IC1-TS{slash}MR)") (class "Default")
      (node (ref "IC1") (pin "D1") (pinfunction "TS/MR_D1") (pintype "bidirectional"))
      (node (ref "R9") (pin "2") (pinfunction "2_2") (pintype "bidirectional"))
    )
    (net (code "43") (name "Net-(IC2-REG)") (class "Default")
      (node (ref "C32") (pin "1") (pinfunction "1_1") (pintype "passive"))
      (node (ref "IC2") (pin "A2") (pinfunction "REG_A2") (pintype "bidirectional"))
    )
    (net (code "44") (name "Net-(IC3-SDO)") (class "Default")
      (node (ref "IC3") (pin "1") (pinfunction "SDO_1") (pintype "bidirectional"))
      (node (ref "R3") (pin "2") (pinfunction "2_2") (pintype "bidirectional"))
    )
    (net (code "45") (name "Net-(IC9-SCL)") (class "Default")
      (node (ref "IC9") (pin "D1") (pinfunction "SCL_D1") (pintype "bidirectional"))
      (node (ref "R4") (pin "2") (pinfunction "2_2") (pintype "bidirectional"))
    )
    (net (code "46") (name "Net-(IC9-SDA)") (class "Default")
      (node (ref "IC9") (pin "E1") (pinfunction "SDA_E1") (pintype "bidirectional"))
      (node (ref "R2") (pin "2") (pinfunction "2_2") (pintype "bidirectional"))
    )
    (net (code "47") (name "Net-(J4-CC1)") (class "Default")
      (node (ref "J4") (pin "A5") (pinfunction "CC1_A5") (pintype "bidirectional"))
      (node (ref "R1_USB") (pin "2") (pinfunction "2_2") (pintype "bidirectional"))
    )
    (net (code "48") (name "Net-(J4-CC2)") (class "Default")
      (node (ref "J4") (pin "B5") (pinfunction "CC2_B5") (pintype "bidirectional"))
      (node (ref "R2_USB") (pin "1") (pinfunction "1_1") (pintype "bidirectional"))
    )
    (net (code "49") (name "Net-(L1-Pad2)") (class "Default")
      (node (ref "L1") (pin "2") (pinfunction "2_2") (pintype "bidirectional"))
      (node (ref "L2") (pin "1") (pinfunction "1_1") (pintype "bidirectional"))
    )
    (net (code "50") (name "Net-(R1_EP_DR-Pad1)") (class "Default")
      (node (ref "R1_EP_DR") (pin "1") (pinfunction "1_1") (pintype "bidirectional"))
      (node (ref "R_TYPE_SEL") (pin "2") (pinfunction "2_2") (pintype "bidirectional"))
      (node (ref "SJ1") (pin "2") (pinfunction "2_2") (pintype "passive"))
    )
    (net (code "51") (name "Net-(U$1-ANT)") (class "Default")
      (node (ref "C3") (pin "1") (pinfunction "1_1") (pintype "passive"))
      (node (ref "L3") (pin "1") (pinfunction "1_1") (pintype "bidirectional"))
      (node (ref "U$1") (pin "P$H23") (pinfunction "ANT_P$H23") (pintype "bidirectional"))
    )
    (net (code "52") (name "Net-(U$1-DCC)") (class "Default")
      (node (ref "L1") (pin "1") (pinfunction "1_1") (pintype "bidirectional"))
      (node (ref "U$1") (pin "P$B3") (pinfunction "DCC_P$B3") (pintype "output"))
    )
    (net (code "53") (name "Net-(U$1-DEC1)") (class "Default")
      (node (ref "C5") (pin "1") (pinfunction "1_1") (pintype "passive"))
      (node (ref "U$1") (pin "P$C1") (pinfunction "DEC1_P$C1") (pintype "power_in"))
    )
    (net (code "54") (name "Net-(U$1-DEC2)") (class "Default")
      (node (ref "C13") (pin "1") (pinfunction "1_1") (pintype "passive"))
      (node (ref "U$1") (pin "P$A18") (pinfunction "DEC2_P$A18") (pintype "bidirectional"))
    )
    (net (code "55") (name "Net-(U$1-DEC3)") (class "Default")
      (node (ref "C11") (pin "1") (pinfunction "1_1") (pintype "passive"))
      (node (ref "U$1") (pin "P$D23") (pinfunction "DEC3_P$D23") (pintype "bidirectional"))
    )
    (net (code "56") (name "Net-(U$1-DEC3V3)") (class "Default")
      (node (ref "C20") (pin "1") (pinfunction "1_1") (pintype "passive"))
      (node (ref "U$1") (pin "P$AC5") (pinfunction "DEC3V3_P$AC5") (pintype "bidirectional"))
    )
    (net (code "57") (name "Net-(U$1-DEC4)") (class "Default")
      (node (ref "C10") (pin "1") (pinfunction "1_1") (pintype "passive"))
      (node (ref "C15") (pin "1") (pinfunction "1_1") (pintype "passive"))
      (node (ref "C16") (pin "1") (pinfunction "1_1") (pintype "passive"))
      (node (ref "L2") (pin "2") (pinfunction "2_2") (pintype "bidirectional"))
      (node (ref "U$1") (pin "P$B5") (pinfunction "DEC4_P$B5") (pintype "power_in"))
      (node (ref "U$1") (pin "P$E24") (pinfunction "DEC6_P$E24") (pintype "bidirectional"))
    )
    (net (code "58") (name "Net-(U$1-DEC5)") (class "Default")
      (node (ref "C9") (pin "1") (pinfunction "1_1") (pintype "passive"))
      (node (ref "U$1") (pin "P$N24") (pinfunction "DEC5_P$N24") (pintype "bidirectional"))
    )
    (net (code "59") (name "Net-(U$1-P0.00{slash}XL1)") (class "Default")
      (node (ref "C17") (pin "2") (pinfunction "2_2") (pintype "passive"))
      (node (ref "U$1") (pin "P$D2") (pinfunction "P0.00/XL1_P$D2") (pintype "bidirectional"))
      (node (ref "XTAL1") (pin "2") (pinfunction "2_2") (pintype "passive"))
    )
    (net (code "60") (name "Net-(U$1-P0.01{slash}XL2)") (class "Default")
      (node (ref "C18") (pin "2") (pinfunction "2_2") (pintype "passive"))
      (node (ref "U$1") (pin "P$F2") (pinfunction "P0.01/XL2_P$F2") (pintype "bidirectional"))
      (node (ref "XTAL1") (pin "1") (pinfunction "1_1") (pintype "passive"))
    )
    (net (code "61") (name "Net-(U$1-XC1)") (class "Default")
      (node (ref "C1") (pin "1") (pinfunction "1_1") (pintype "passive"))
      (node (ref "U$1") (pin "P$B24") (pinfunction "XC1_P$B24") (pintype "input"))
      (node (ref "U$2") (pin "1") (pinfunction "1_1") (pintype "passive"))
    )
    (net (code "62") (name "Net-(U$1-XC2)") (class "Default")
      (node (ref "C2") (pin "1") (pinfunction "1_1") (pintype "passive"))
      (node (ref "U$1") (pin "P$A23") (pinfunction "XC2_P$A23") (pintype "output"))
      (node (ref "U$2") (pin "3") (pinfunction "3_3") (pintype "passive"))
    )
    (net (code "63") (name "OUT+") (class "Default")
      (node (ref "IC2") (pin "A3") (pinfunction "OUT+_A3") (pintype "bidirectional"))
      (node (ref "TP_OP") (pin "TP") (pinfunction "TP_TP") (pintype "input"))
    )
    (net (code "64") (name "OUT-") (class "Default")
      (node (ref "IC2") (pin "C3") (pinfunction "OUT-_C3") (pintype "bidirectional"))
      (node (ref "TP_ON") (pin "TP") (pinfunction "TP_TP") (pintype "input"))
    )
    (net (code "65") (name "P0.04") (class "Default")
      (node (ref "U$1") (pin "P$J1") (pinfunction "P0.04/AIN2_P$J1") (pintype "bidirectional"))
    )
    (net (code "66") (name "P0.09") (class "Default")
      (node (ref "U$1") (pin "P$L24") (pinfunction "P0.09/NFC1_P$L24") (pintype "bidirectional"))
    )
    (net (code "67") (name "P0.13{slash}1.5D") (class "Default")
      (node (ref "C30") (pin "1") (pinfunction "1_1") (pintype "passive"))
      (node (ref "R5") (pin "1") (pinfunction "1_1") (pintype "bidirectional"))
      (node (ref "SW_UP") (pin "2") (pinfunction "2_2") (pintype "passive"))
    )
    (net (code "68") (name "P0.13{slash}2.6C") (class "Default")
      (node (ref "U$1") (pin "P$AD8") (pinfunction "P0.13_P$AD8") (pintype "bidirectional"))
    )
    (net (code "69") (name "P0.14{slash}1.5D") (class "Default")
      (node (ref "C31") (pin "1") (pinfunction "1_1") (pintype "passive"))
      (node (ref "R8") (pin "1") (pinfunction "1_1") (pintype "bidirectional"))
      (node (ref "SW_ENT") (pin "2") (pinfunction "2_2") (pintype "passive"))
    )
    (net (code "70") (name "P0.14{slash}2.7C") (class "Default")
      (node (ref "U$1") (pin "P$AC9") (pinfunction "P0.14_P$AC9") (pintype "bidirectional"))
    )
    (net (code "71") (name "P0.19") (class "Default")
      (node (ref "U$1") (pin "P$AC15") (pinfunction "P0.19_P$AC15") (pintype "bidirectional"))
    )
    (net (code "72") (name "P0.20") (class "Default")
      (node (ref "U$1") (pin "P$AD16") (pinfunction "P0.20_P$AD16") (pintype "bidirectional"))
    )
    (net (code "73") (name "P0.21") (class "Default")
      (node (ref "U$1") (pin "P$AC17") (pinfunction "P0.21_P$AC17") (pintype "bidirectional"))
    )
    (net (code "74") (name "P0.22") (class "Default")
      (node (ref "U$1") (pin "P$AD18") (pinfunction "P0.22_P$AD18") (pintype "bidirectional"))
    )
    (net (code "75") (name "P0.23") (class "Default")
      (node (ref "U$1") (pin "P$AC19") (pinfunction "P0.23_P$AC19") (pintype "bidirectional"))
    )
    (net (code "76") (name "P0.24") (class "Default")
      (node (ref "U$1") (pin "P$AD20") (pinfunction "P0.24_P$AD20") (pintype "bidirectional"))
    )
    (net (code "77") (name "P0.25") (class "Default")
      (node (ref "U$1") (pin "P$AC21") (pinfunction "P0.25_P$AC21") (pintype "bidirectional"))
    )
    (net (code "78") (name "P0.26") (class "Default")
      (node (ref "U$1") (pin "P$G1") (pinfunction "P0.26_P$G1") (pintype "bidirectional"))
    )
    (net (code "79") (name "P0.27") (class "Default")
      (node (ref "U$1") (pin "P$H2") (pinfunction "P0.27_P$H2") (pintype "bidirectional"))
    )
    (net (code "80") (name "P0.28") (class "Default")
      (node (ref "U$1") (pin "P$B11") (pinfunction "P0.28/AIN4_P$B11") (pintype "bidirectional"))
    )
    (net (code "81") (name "P0.29") (class "Default")
      (node (ref "U$1") (pin "P$A10") (pinfunction "P0.29/AIN5_P$A10") (pintype "bidirectional"))
    )
    (net (code "82") (name "P0.30") (class "Default")
      (node (ref "U$1") (pin "P$B9") (pinfunction "P0.30/AIN6_P$B9") (pintype "bidirectional"))
    )
    (net (code "83") (name "P0.31") (class "Default")
      (node (ref "U$1") (pin "P$A8") (pinfunction "P0.31/AIN7_P$A8") (pintype "bidirectional"))
    )
    (net (code "84") (name "P1.01{slash}1.6C") (class "Default")
      (node (ref "Q1") (pin "1") (pinfunction "G_1") (pintype "bidirectional"))
      (node (ref "R_PWR_EPD") (pin "1") (pinfunction "1_1") (pintype "bidirectional"))
    )
    (net (code "85") (name "P1.01{slash}2.4B") (class "Default")
      (node (ref "U$1") (pin "P$Y23") (pinfunction "P1.01_P$Y23") (pintype "bidirectional"))
    )
    (net (code "86") (name "P1.02{slash}1.6C") (class "Default")
      (node (ref "C29") (pin "1") (pinfunction "1_1") (pintype "passive"))
      (node (ref "R7") (pin "1") (pinfunction "1_1") (pintype "bidirectional"))
      (node (ref "SW_DN") (pin "2") (pinfunction "2_2") (pintype "passive"))
    )
    (net (code "87") (name "P1.02{slash}2.8C") (class "Default")
      (node (ref "U$1") (pin "P$W24") (pinfunction "P1.02_P$W24") (pintype "bidirectional"))
    )
    (net (code "88") (name "P1.03") (class "Default")
      (node (ref "U$1") (pin "P$V23") (pinfunction "P1.03_P$V23") (pintype "bidirectional"))
    )
    (net (code "89") (name "P1.04") (class "Default")
      (node (ref "U$1") (pin "P$U24") (pinfunction "P1.04_P$U24") (pintype "bidirectional"))
    )
    (net (code "90") (name "P1.05") (class "Default")
      (node (ref "U$1") (pin "P$T23") (pinfunction "P1.05_P$T23") (pintype "bidirectional"))
    )
    (net (code "91") (name "P1.06") (class "Default")
      (node (ref "U$1") (pin "P$R24") (pinfunction "P1.06_P$R24") (pintype "bidirectional"))
    )
    (net (code "92") (name "P1.07") (class "Default")
      (node (ref "U$1") (pin "P$P23") (pinfunction "P1.07_P$P23") (pintype "bidirectional"))
    )
    (net (code "93") (name "P1.09") (class "Default")
      (node (ref "U$1") (pin "P$R1") (pinfunction "P1.09_P$R1") (pintype "bidirectional"))
    )
    (net (code "94") (name "P1.10") (class "Default")
      (node (ref "U$1") (pin "P$A20") (pinfunction "P1.10_P$A20") (pintype "bidirectional"))
    )
    (net (code "95") (name "P1.11") (class "Default")
      (node (ref "U$1") (pin "P$B19") (pinfunction "P1.11_P$B19") (pintype "bidirectional"))
    )
    (net (code "96") (name "P1.12") (class "Default")
      (node (ref "U$1") (pin "P$B17") (pinfunction "P1.12_P$B17") (pintype "bidirectional"))
    )
    (net (code "97") (name "P1.13") (class "Default")
      (node (ref "U$1") (pin "P$A16") (pinfunction "P1.13_P$A16") (pintype "bidirectional"))
    )
    (net (code "98") (name "P1.14") (class "Default")
      (node (ref "U$1") (pin "P$B15") (pinfunction "P1.14_P$B15") (pintype "bidirectional"))
    )
    (net (code "99") (name "P1.15") (class "Default")
      (node (ref "U$1") (pin "P$A14") (pinfunction "P1.15_P$A14") (pintype "bidirectional"))
    )
    (net (code "100") (name "PMIC_INT") (class "Default")
      (node (ref "IC1") (pin "A1") (pinfunction "~{INT}_A1") (pintype "bidirectional"))
      (node (ref "U$1") (pin "P$T2") (pinfunction "P0.11_P$T2") (pintype "bidirectional"))
    )
    (net (code "101") (name "PREVGH") (class "Default")
      (node (ref "D5") (pin "1") (pinfunction "K_1") (pintype "bidirectional"))
    )
    (net (code "102") (name "PREVGL") (class "Default")
      (node (ref "D2") (pin "2") (pinfunction "A_2") (pintype "bidirectional"))
    )
    (net (code "103") (name "RESE") (class "Default")
      (node (ref "J2") (pin "3") (pinfunction "3_3") (pintype "bidirectional"))
      (node (ref "Q3") (pin "2") (pinfunction "S_2") (pintype "bidirectional"))
      (node (ref "R1_EP_DR") (pin "2") (pinfunction "2_2") (pintype "bidirectional"))
    )
    (net (code "104") (name "RESET") (class "Default")
      (node (ref "J1") (pin "6") (pinfunction "6_6") (pintype "bidirectional"))
      (node (ref "TP_RESET") (pin "TP") (pinfunction "TP_TP") (pintype "input"))
      (node (ref "U$1") (pin "P$AC13") (pinfunction "P0.18/RESET_P$AC13") (pintype "bidirectional"))
    )
    (net (code "105") (name "SCK{slash}1.5B") (class "Default")
      (node (ref "J2") (pin "13") (pinfunction "13_13") (pintype "bidirectional"))
    )
    (net (code "106") (name "SCK{slash}2.2D") (class "Default")
      (node (ref "U$1") (pin "P$A12") (pinfunction "P0.02/AIN0_P$A12") (pintype "bidirectional"))
    )
    (net (code "107") (name "SCL{slash}1.4C") (class "Default")
      (node (ref "IC2") (pin "C1") (pinfunction "SCL_C1") (pintype "bidirectional"))
      (node (ref "U3") (pin "7") (pinfunction "SCL_7") (pintype "input"))
    )
    (net (code "108") (name "SCL{slash}2.4C") (class "Default")
      (node (ref "IC1") (pin "B1") (pinfunction "SCL_B1") (pintype "bidirectional"))
      (node (ref "IC3") (pin "12") (pinfunction "SCX_12") (pintype "bidirectional"))
      (node (ref "R17") (pin "2") (pinfunction "2_2") (pintype "bidirectional"))
      (node (ref "R4") (pin "1") (pinfunction "1_1") (pintype "bidirectional"))
      (node (ref "TP_SCL") (pin "TP") (pinfunction "TP_TP") (pintype "input"))
      (node (ref "U$1") (pin "P$M2") (pinfunction "P0.07_P$M2") (pintype "bidirectional"))
    )
    (net (code "109") (name "SDA{slash}1.4C") (class "Default")
      (node (ref "IC2") (pin "B2") (pinfunction "SDA_B2") (pintype "bidirectional"))
      (node (ref "U3") (pin "8") (pinfunction "SDA_8") (pintype "bidirectional"))
    )
    (net (code "110") (name "SDA{slash}2.4C") (class "Default")
      (node (ref "IC1") (pin "C1") (pinfunction "SDA_C1") (pintype "bidirectional"))
      (node (ref "IC3") (pin "2") (pinfunction "SDX_2") (pintype "bidirectional"))
      (node (ref "R18") (pin "2") (pinfunction "2_2") (pintype "bidirectional"))
      (node (ref "R2") (pin "1") (pinfunction "1_1") (pintype "bidirectional"))
      (node (ref "TP_SDA") (pin "TP") (pinfunction "TP_TP") (pintype "input"))
      (node (ref "U$1") (pin "P$L1") (pinfunction "P0.06_P$L1") (pintype "bidirectional"))
    )
    (net (code "111") (name "SWDCLK") (class "Default")
      (node (ref "J1") (pin "4") (pinfunction "4_4") (pintype "bidirectional"))
      (node (ref "TP_SWDCLK") (pin "TP") (pinfunction "TP_TP") (pintype "input"))
      (node (ref "U$1") (pin "P$AA24") (pinfunction "SWDCLK_P$AA24") (pintype "input"))
    )
    (net (code "112") (name "SWDIO") (class "Default")
      (node (ref "TP_SWDIO") (pin "TP") (pinfunction "TP_TP") (pintype "input"))
      (node (ref "U$1") (pin "P$AC24") (pinfunction "SWDIO_P$AC24") (pintype "bidirectional"))
    )
    (net (code "113") (name "SWO") (class "Default")
      (node (ref "TP_SWO") (pin "TP") (pinfunction "TP_TP") (pintype "input"))
      (node (ref "U$1") (pin "P$AD22") (pinfunction "P1.00_P$AD22") (pintype "bidirectional"))
    )
    (net (code "114") (name "VBAT{slash}1.2A") (class "Default")
      (node (ref "C27") (pin "1") (pinfunction "1_1") (pintype "passive"))
      (node (ref "TP_VBAT") (pin "TP") (pinfunction "TP_TP") (pintype "input"))
      (node (ref "U3") (pin "2") (pinfunction "CELL_2") (pintype "power_in"))
      (node (ref "U3") (pin "3") (pinfunction "VDD_3") (pintype "power_in"))
    )
    (net (code "115") (name "VBAT{slash}2.5C") (class "Default")
      (node (ref "C37") (pin "1") (pinfunction "1_1") (pintype "passive"))
      (node (ref "IC1") (pin "C2") (pinfunction "BAT_C2") (pintype "bidirectional"))
    )
    (net (code "116") (name "VBUS{slash}1.5D") (class "Default")
      (node (ref "C42") (pin "1") (pinfunction "1_1") (pintype "passive"))
      (node (ref "C43") (pin "1") (pinfunction "1_1") (pintype "passive"))
      (node (ref "D1") (pin "5") (pinfunction "VBUS_5") (pintype "bidirectional"))
      (node (ref "J4") (pin "A4_B9") (pinfunction "VBUS_A4_B9") (pintype "power_in"))
      (node (ref "J4") (pin "A9_B4") (pinfunction "VBUS_A9_B4") (pintype "power_in"))
    )
    (net (code "117") (name "VBUS{slash}2.6D") (class "Default")
      (node (ref "C21") (pin "1") (pinfunction "1_1") (pintype "passive"))
      (node (ref "C38") (pin "1") (pinfunction "1_1") (pintype "passive"))
      (node (ref "IC1") (pin "A2") (pinfunction "IN_A2") (pintype "bidirectional"))
      (node (ref "U$1") (pin "P$AD2") (pinfunction "VBUS_P$AD2") (pintype "power_in"))
    )
    (net (code "118") (name "VREG") (class "Default")
      (node (ref "C23") (pin "2") (pinfunction "2_2") (pintype "passive"))
      (node (ref "C24") (pin "2") (pinfunction "2_2") (pintype "passive"))
      (node (ref "C39") (pin "1") (pinfunction "1_1") (pintype "passive"))
      (node (ref "IC1") (pin "B2") (pinfunction "SYS_B2") (pintype "bidirectional"))
      (node (ref "IC9") (pin "A1") (pinfunction "EN_A1") (pintype "bidirectional"))
      (node (ref "IC9") (pin "A2") (pinfunction "VIN_1_A2") (pintype "bidirectional"))
      (node (ref "IC9") (pin "A3") (pinfunction "VIN_2_A3") (pintype "bidirectional"))
      (node (ref "TP_VREG") (pin "TP") (pinfunction "TP_TP") (pintype "input"))
    )
    (net (code "119") (name "unconnected-(ANT1-NC-Pad2)") (class "Default")
      (node (ref "ANT1") (pin "2") (pinfunction "NC_2") (pintype "no_connect"))
    )
    (net (code "120") (name "unconnected-(IC3-ASCL-Pad11)") (class "Default")
      (node (ref "IC3") (pin "11") (pinfunction "ASCL_11") (pintype "bidirectional"))
    )
    (net (code "121") (name "unconnected-(IC3-ASDA-Pad4)") (class "Default")
      (node (ref "IC3") (pin "4") (pinfunction "ASDA_4") (pintype "bidirectional"))
    )
    (net (code "122") (name "unconnected-(J1-Pad2)") (class "Default")
      (node (ref "J1") (pin "2") (pinfunction "2_2") (pintype "bidirectional"))
    )
    (net (code "123") (name "unconnected-(J2-Pad1)") (class "Default")
      (node (ref "J2") (pin "1") (pinfunction "1_1") (pintype "bidirectional"))
    )
    (net (code "124") (name "unconnected-(J2-Pad6)") (class "Default")
      (node (ref "J2") (pin "6") (pinfunction "6_6") (pintype "bidirectional"))
    )
    (net (code "125") (name "unconnected-(J2-Pad7)") (class "Default")
      (node (ref "J2") (pin "7") (pinfunction "7_7") (pintype "bidirectional"))
    )
    (net (code "126") (name "unconnected-(J4-SBU1-PadA8)") (class "Default")
      (node (ref "J4") (pin "A8") (pinfunction "SBU1_A8") (pintype "bidirectional"))
    )
    (net (code "127") (name "unconnected-(J4-SBU2-PadB8)") (class "Default")
      (node (ref "J4") (pin "B8") (pinfunction "SBU2_B8") (pintype "bidirectional"))
    )
    (net (code "128") (name "unconnected-(U$1-DCCH-PadP$AB2)") (class "Default")
      (node (ref "U$1") (pin "P$AB2") (pinfunction "DCCH_P$AB2") (pintype "bidirectional"))
    )
  )
)
